# working.net
KiCad netlist of a schematic drawn in EAGLE
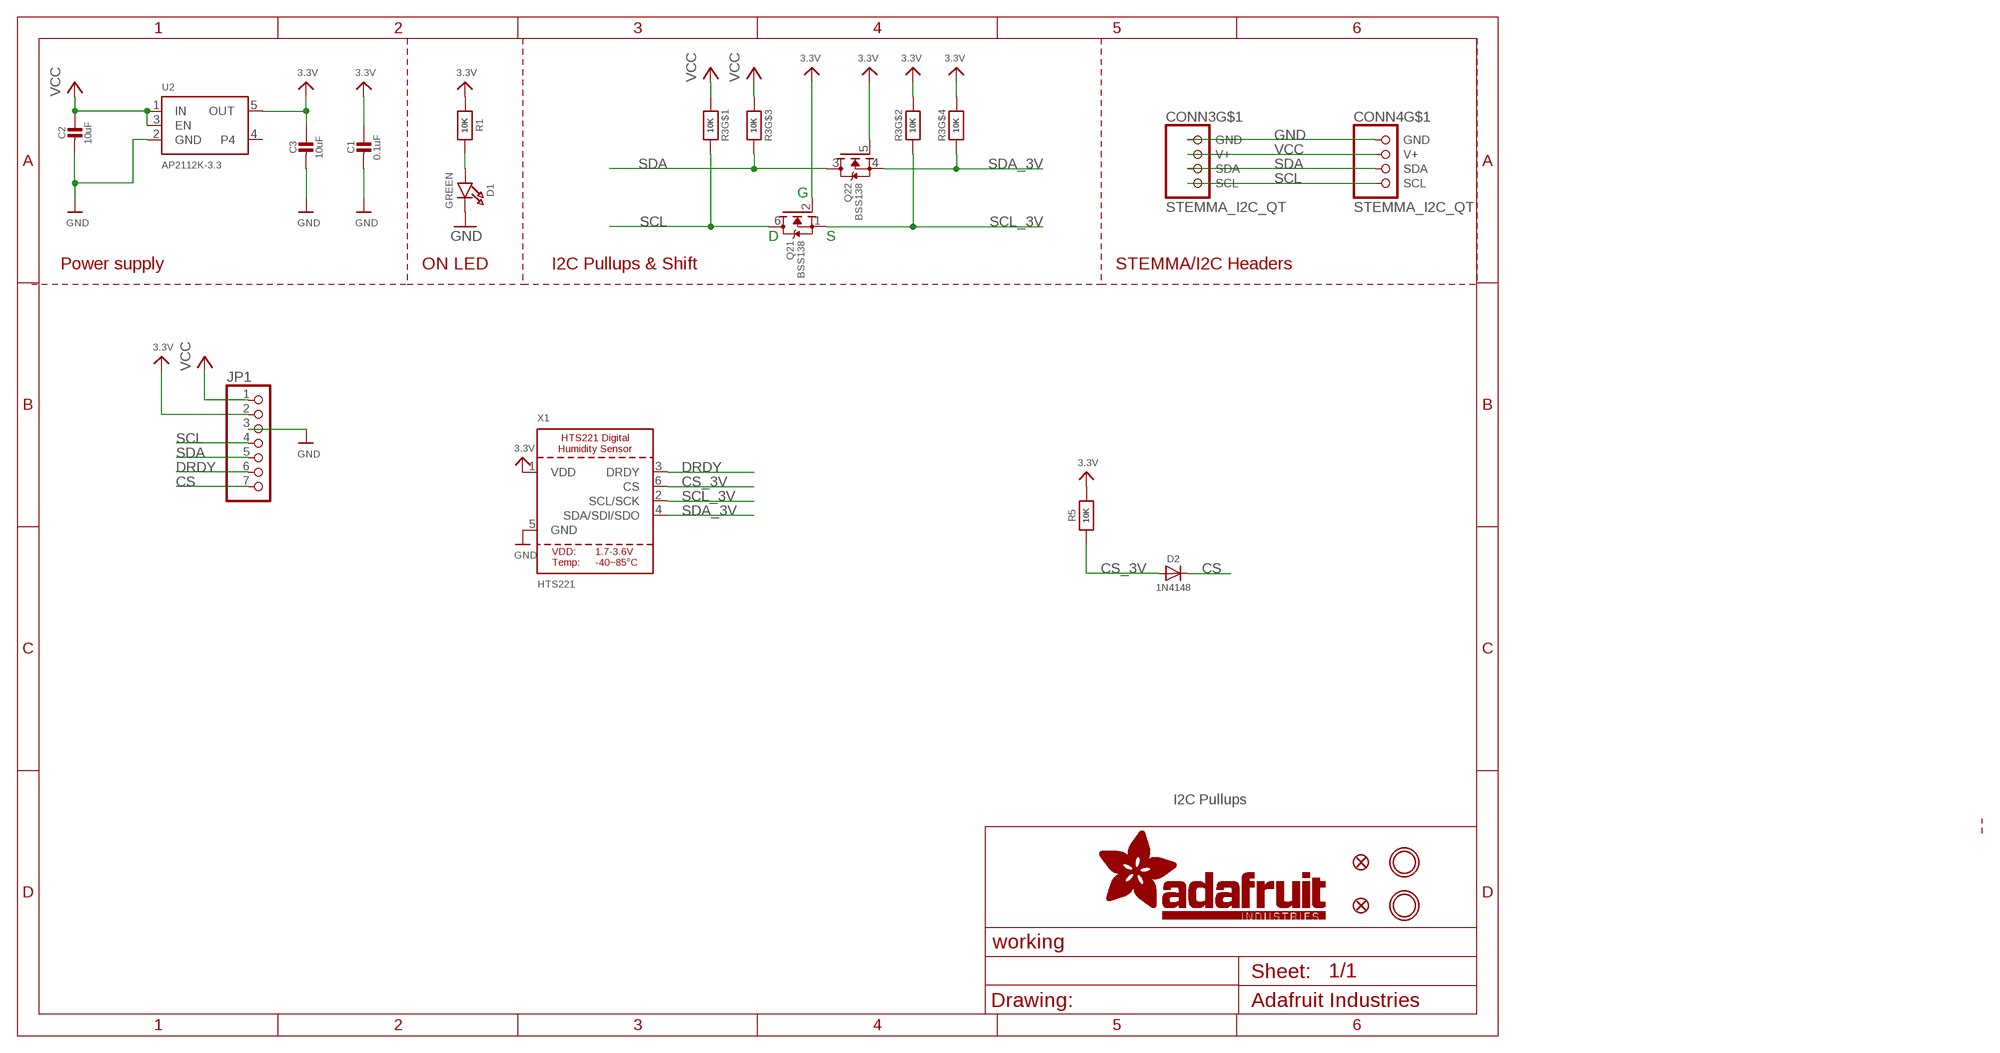
[diagram p0: schematic, sheet 1]

(export (version "E")
  (design (tool "Eeschema 10.0.6"))
  (components
    (comp (ref "C1")
      (value "0.1uF")
      (footprint "eagle-import:0603-NO")
      (libsource (lib "eagle-import") (part "CAP_CERAMIC0603_NO"))
    )
    (comp (ref "C2")
      (value "10uF")
      (footprint "eagle-import:0805-NO")
      (libsource (lib "eagle-import") (part "CAP_CERAMIC0805-NOOUTLINE"))
    )
    (comp (ref "C3")
      (value "10uF")
      (footprint "eagle-import:0805-NO")
      (libsource (lib "eagle-import") (part "CAP_CERAMIC0805-NOOUTLINE"))
    )
    (comp (ref "CONN3")
      (value "STEMMA_I2C_QT")
      (footprint "eagle-import:JST_SH4")
      (libsource (lib "eagle-import") (part "STEMMA_I2C_QT"))
    )
    (comp (ref "CONN4")
      (value "STEMMA_I2C_QT")
      (footprint "eagle-import:JST_SH4")
      (libsource (lib "eagle-import") (part "STEMMA_I2C_QT"))
    )
    (comp (ref "D1")
      (value "GREEN")
      (footprint "eagle-import:CHIPLED_0603_NOOUTLINE")
      (libsource (lib "eagle-import") (part "LED0603_NOOUTLINE"))
    )
    (comp (ref "D2")
      (value "1N4148")
      (footprint "eagle-import:SOD-323")
      (libsource (lib "eagle-import") (part "DIODESOD-323"))
    )
    (comp (ref "FID3")
      (value "FIDUCIAL_1MM")
      (footprint "eagle-import:FIDUCIAL_1MM")
      (libsource (lib "eagle-import") (part "FIDUCIAL_1MM"))
    )
    (comp (ref "FID4")
      (value "FIDUCIAL_1MM")
      (footprint "eagle-import:FIDUCIAL_1MM")
      (libsource (lib "eagle-import") (part "FIDUCIAL_1MM"))
    )
    (comp (ref "JP1")
      (value "HEADER-1X770MIL")
      (footprint "eagle-import:1X07_ROUND_70")
      (libsource (lib "eagle-import") (part "HEADER-1X770MIL"))
    )
    (comp (ref "Q2")
      (value "BSS138")
      (footprint "eagle-import:SOT363")
      (libsource (lib "eagle-import") (part "MOSFET-N_DUAL"))
    )
    (comp (ref "R1")
      (value "10K")
      (footprint "eagle-import:0603-NO")
      (libsource (lib "eagle-import") (part "RESISTOR_0603_NOOUT"))
    )
    (comp (ref "R3")
      (value "10K")
      (footprint "eagle-import:RESPACK_4X0603")
      (libsource (lib "eagle-import") (part "RESISTOR_4PACK"))
    )
    (comp (ref "R5")
      (value "10K")
      (footprint "eagle-import:0603-NO")
      (libsource (lib "eagle-import") (part "RESISTOR_0603_NOOUT"))
    )
    (comp (ref "U$1")
      (value "MOUNTINGHOLE2.5")
      (footprint "eagle-import:MOUNTINGHOLE_2.5_PLATED")
      (libsource (lib "eagle-import") (part "MOUNTINGHOLE2.5"))
    )
    (comp (ref "U$17")
      (value "MOUNTINGHOLE2.5")
      (footprint "eagle-import:MOUNTINGHOLE_2.5_PLATED")
      (libsource (lib "eagle-import") (part "MOUNTINGHOLE2.5"))
    )
    (comp (ref "U2")
      (value "AP2112K-3.3")
      (footprint "eagle-import:SOT23-5")
      (libsource (lib "eagle-import") (part "VREG_SOT23-5"))
    )
    (comp (ref "X1")
      (value "HTS221")
      (footprint "eagle-import:HLGA-6L")
      (libsource (lib "eagle-import") (part "HTS221"))
    )
  )
  (nets
    (net (code "1") (name "/CS") (class "Default")
      (node (ref "D2") (pin "C") (pinfunction "C_C") (pintype "passive"))
      (node (ref "JP1") (pin "7") (pinfunction "7_7") (pintype "passive"))
    )
    (net (code "2") (name "/CS_3V") (class "Default")
      (node (ref "D2") (pin "A") (pinfunction "A_A") (pintype "passive"))
      (node (ref "R5") (pin "1") (pinfunction "1_1") (pintype "passive"))
      (node (ref "X1") (pin "6") (pinfunction "CS_6") (pintype "input"))
    )
    (net (code "3") (name "/DRDY") (class "Default")
      (node (ref "JP1") (pin "6") (pinfunction "6_6") (pintype "passive"))
      (node (ref "X1") (pin "3") (pinfunction "DRDY_3") (pintype "output"))
    )
    (net (code "4") (name "/SCL") (class "Default")
      (node (ref "CONN3") (pin "4") (pinfunction "SCL_4") (pintype "passive"))
      (node (ref "CONN4") (pin "4") (pinfunction "SCL_4") (pintype "passive"))
      (node (ref "JP1") (pin "4") (pinfunction "4_4") (pintype "passive"))
      (node (ref "Q2") (pin "6") (pinfunction "D_6") (pintype "bidirectional"))
      (node (ref "R3") (pin "8") (pinfunction "2_8") (pintype "passive"))
    )
    (net (code "5") (name "/SCL_3V") (class "Default")
      (node (ref "Q2") (pin "1") (pinfunction "S_1") (pintype "bidirectional"))
      (node (ref "R3") (pin "7") (pinfunction "2_7") (pintype "passive"))
      (node (ref "X1") (pin "2") (pinfunction "SCL/SCK_2") (pintype "input"))
    )
    (net (code "6") (name "/SDA") (class "Default")
      (node (ref "CONN3") (pin "3") (pinfunction "SDA_3") (pintype "passive"))
      (node (ref "CONN4") (pin "3") (pinfunction "SDA_3") (pintype "passive"))
      (node (ref "JP1") (pin "5") (pinfunction "5_5") (pintype "passive"))
      (node (ref "Q2") (pin "3") (pinfunction "D_3") (pintype "bidirectional"))
      (node (ref "R3") (pin "6") (pinfunction "2_6") (pintype "passive"))
    )
    (net (code "7") (name "/SDA_3V") (class "Default")
      (node (ref "Q2") (pin "4") (pinfunction "S_4") (pintype "bidirectional"))
      (node (ref "R3") (pin "5") (pinfunction "2_5") (pintype "passive"))
      (node (ref "X1") (pin "4") (pinfunction "SDA/SDI/SDO_4") (pintype "output"))
    )
    (net (code "8") (name "3.3V") (class "Default")
      (node (ref "C1") (pin "1") (pinfunction "1_1") (pintype "passive"))
      (node (ref "C3") (pin "1") (pinfunction "1_1") (pintype "passive"))
      (node (ref "JP1") (pin "2") (pinfunction "2_2") (pintype "passive"))
      (node (ref "Q2") (pin "2") (pinfunction "G_2") (pintype "bidirectional"))
      (node (ref "Q2") (pin "5") (pinfunction "G_5") (pintype "bidirectional"))
      (node (ref "R1") (pin "1") (pinfunction "1_1") (pintype "passive"))
      (node (ref "R3") (pin "2") (pinfunction "1_2") (pintype "passive"))
      (node (ref "R3") (pin "4") (pinfunction "1_4") (pintype "passive"))
      (node (ref "R5") (pin "2") (pinfunction "2_2") (pintype "passive"))
      (node (ref "U2") (pin "5") (pinfunction "OUT_5") (pintype "power_in"))
      (node (ref "X1") (pin "1") (pinfunction "VDD_1") (pintype "power_in"))
    )
    (net (code "9") (name "GND") (class "Default")
      (node (ref "C1") (pin "2") (pinfunction "2_2") (pintype "passive"))
      (node (ref "C2") (pin "2") (pinfunction "2_2") (pintype "passive"))
      (node (ref "C3") (pin "2") (pinfunction "2_2") (pintype "passive"))
      (node (ref "CONN3") (pin "1") (pinfunction "GND_1") (pintype "passive"))
      (node (ref "CONN4") (pin "1") (pinfunction "GND_1") (pintype "passive"))
      (node (ref "D1") (pin "C") (pinfunction "C_C") (pintype "passive"))
      (node (ref "JP1") (pin "3") (pinfunction "3_3") (pintype "passive"))
      (node (ref "U2") (pin "2") (pinfunction "GND_2") (pintype "power_in"))
      (node (ref "X1") (pin "5") (pinfunction "GND_5") (pintype "power_in"))
    )
    (net (code "10") (name "Net-(D1-PadA)") (class "Default")
      (node (ref "D1") (pin "A") (pinfunction "A_A") (pintype "passive"))
      (node (ref "R1") (pin "2") (pinfunction "2_2") (pintype "passive"))
    )
    (net (code "11") (name "VCC") (class "Default")
      (node (ref "C2") (pin "1") (pinfunction "1_1") (pintype "passive"))
      (node (ref "CONN3") (pin "2") (pinfunction "V+_2") (pintype "passive"))
      (node (ref "CONN4") (pin "2") (pinfunction "V+_2") (pintype "passive"))
      (node (ref "JP1") (pin "1") (pinfunction "1_1") (pintype "passive"))
      (node (ref "R3") (pin "1") (pinfunction "1_1") (pintype "passive"))
      (node (ref "R3") (pin "3") (pinfunction "1_3") (pintype "passive"))
      (node (ref "U2") (pin "1") (pinfunction "IN_1") (pintype "power_in"))
      (node (ref "U2") (pin "3") (pinfunction "EN_3") (pintype "input"))
    )
    (net (code "12") (name "unconnected-(U2-P4-Pad4)") (class "Default")
      (node (ref "U2") (pin "4") (pinfunction "P4_4") (pintype "bidirectional"))
    )
  )
)
